# Sheet1.net
KiCad netlist of a schematic drawn in Altium Designer
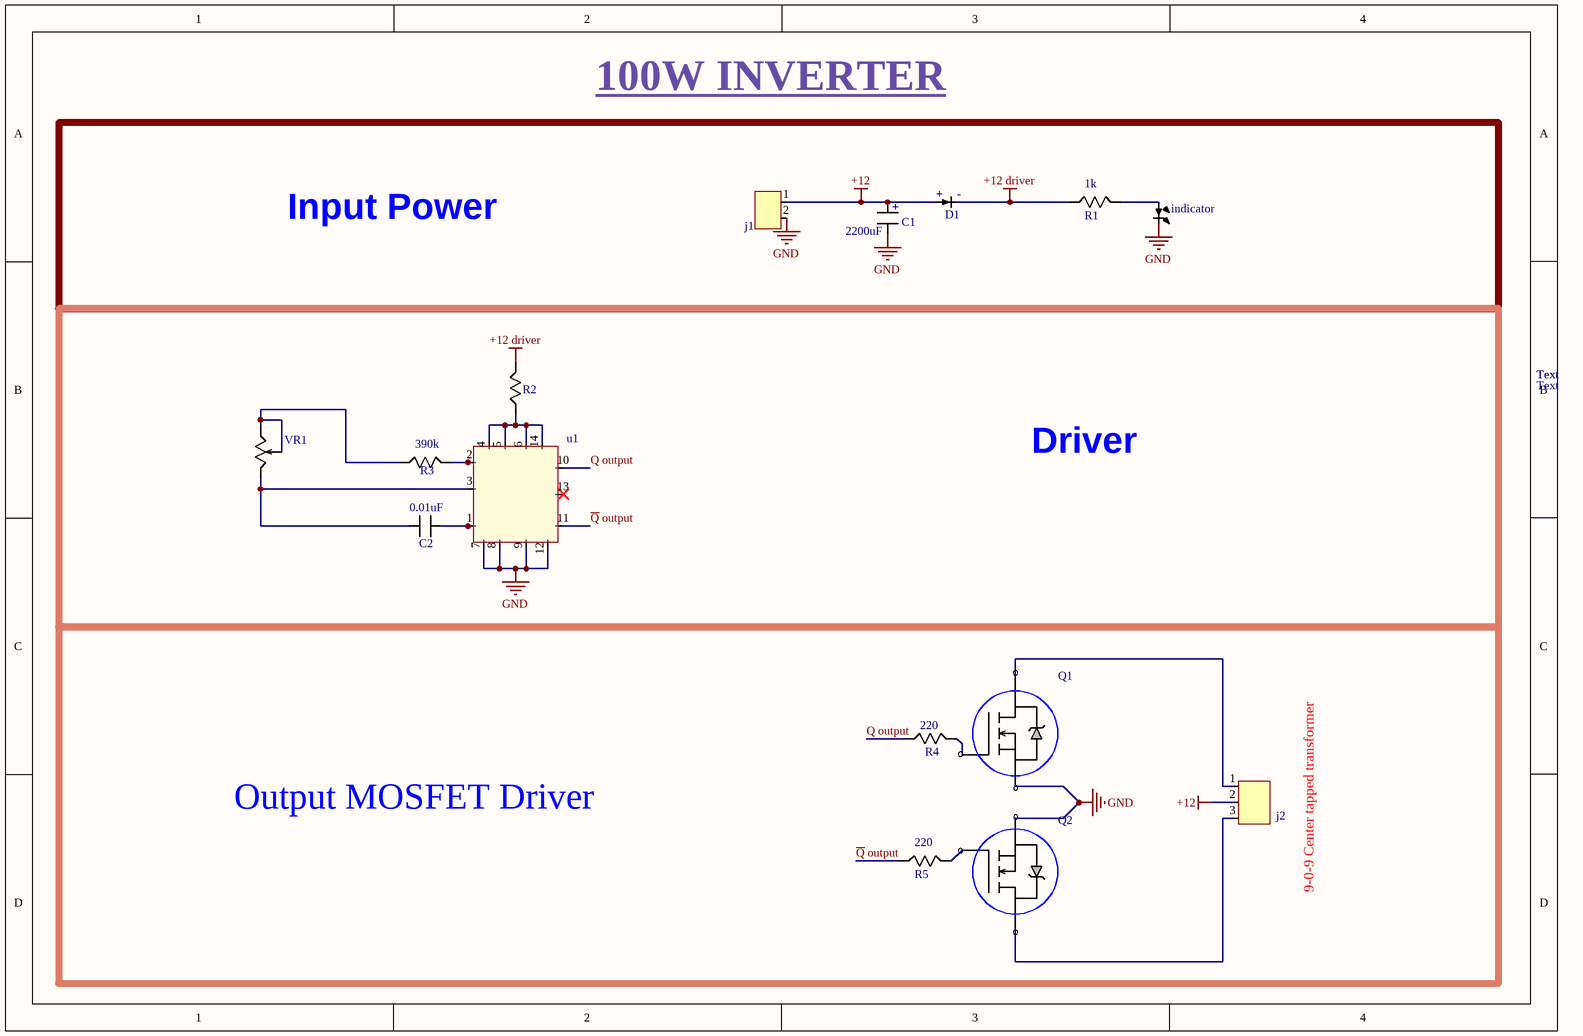
[diagram p0: Sheet1.SchDoc]

(export (version "E")
  (design (tool "Eeschema 10.0.6"))
  (components
    (comp (ref "1")
      (value "D1")
      (footprint "1N4007_TH_D")
      (description "Diode Switching 1KV 1A 2-Pin DO-41 T/R")
      (libsource (lib "Sch_common.~(3)") (part "D_1N400_th"))
    )
    (comp (ref "C1")
      (value "2200uF")
      (footprint "2200uF_35V_Ely_TH")
      (fields (field (name "TOLERANCE") "20%"))
      (libsource (lib "Sch_common.~(3)") (part "C_2200uF_Ely_35V_TH"))
    )
    (comp (ref "C2")
      (value "0.01uF")
      (footprint "0.01uF_cer_th_C - duplicate1")
      (description "Capacitor Ceramic 0.01uF 50V C0G 5% 5mm T/R")
      (fields (field (name "TOLERANCE") "5%"))
      (libsource (lib "Sch_common.~(3)") (part "C_0.01uF_Cer_50V_TH"))
    )
    (comp (ref "indicator")
      (value "LED_3mm_red_TH")
      (footprint "LED_red_TH")
      (libsource (lib "Sch_common.~(3)") (part "LED_3mm_red_TH"))
    )
    (comp (ref "j1")
      (value "2P_5mm_TH")
      (footprint "2pin_5mm_TH")
      (description "TERM BLOCK PLUG 2POS 90DEG 5MM")
      (fields (field (name "VOLTAGE") "300V"))
      (libsource (lib "Sch_common.~(3)") (part "2P_5mm_TH"))
    )
    (comp (ref "j2")
      (value "3pin_5mm_TH")
      (footprint "3pin_5mm_TH")
      (description "Connector Terminal Blocks Female 3 Position 5mm Screw Straig")
      (fields (field (name "VOLTAGE") "300V"))
      (libsource (lib "Sch_common.~(3)") (part "3pin_5mm_TH"))
    )
    (comp (ref "Q1")
      (value "IRF540ZLPBF")
      (footprint "IRF540_TH_MOS")
      (description "Mosfet, Power; N-ch; Vdss 100V; Rds(on) 21MILLIOHMS; Id 36A; TO-262; Pd 92W; Vgs +/-20")
      (libsource (lib "Sch_common.~(3)") (part "IRF540ZLPBF"))
    )
    (comp (ref "Q2")
      (value "IRF540ZLPBF")
      (footprint "IRF540_TH_MOS")
      (description "Mosfet, Power; N-ch; Vdss 100V; Rds(on) 21MILLIOHMS; Id 36A; TO-262; Pd 92W; Vgs +/-20")
      (libsource (lib "Sch_common.~(3)") (part "IRF540ZLPBF"))
    )
    (comp (ref "R1")
      (value "1k")
      (footprint "1k_0.25_th_R")
      (description "TE Connectivity CFR16 Series Axial Carbon Film Resistor 1k 5% 0.25W -1200  0ppm/C")
      (fields (field (name "TOLERANCE") "5%"))
      (libsource (lib "Sch_common.~(3)") (part "R_1K_0.25W_TH"))
    )
    (comp (ref "R2")
      (value "R_330_0.25W_TH")
      (footprint "330ohm_th_R")
      (description "TE Connectivity CFR16 Series Axial Carbon Film Resistor 330 5% 0.25W -1200  0ppm/C")
      (fields (field (name "TOLERANCE") "5%"))
      (libsource (lib "Sch_common.~(3)") (part "R_330_0.25W_TH"))
    )
    (comp (ref "R3")
      (value "390k")
      (footprint "390ohm_0.25w_th_R")
      (description "RES 390K OHM 1/4W 5% AXIAL")
      (fields (field (name "TOLERANCE") "5%"))
      (libsource (lib "Sch_common.~(3)") (part "R_390K_0.25W_TH"))
    )
    (comp (ref "R4")
      (value "220")
      (footprint "220ohm_0.25_th_R")
      (description "RES 220 OHM 1/4W 5% AXIAL")
      (fields (field (name "TOLERANCE") "5%"))
      (libsource (lib "Sch_common.~(3)") (part "R_220_0.25W_TH"))
    )
    (comp (ref "R5")
      (value "220")
      (footprint "220ohm_0.25_th_R")
      (description "RES 220 OHM 1/4W 5% AXIAL")
      (fields (field (name "TOLERANCE") "5%"))
      (libsource (lib "Sch_common.~(3)") (part "R_220_0.25W_TH"))
    )
    (comp (ref "u1")
      (value "CD4047BE IC")
      (footprint "CD4047_TH_IC")
      (libsource (lib "Sch_common.~(3)") (part "CD4047BE IC"))
    )
    (comp (ref "VR1")
      (value "VR_1K_trim_20T")
      (footprint "1k_var_th_R")
      (description "TRIMMER 1K OHM 1W PC PIN")
      (fields (field (name "TOLERANCE") "5%"))
      (libsource (lib "Sch_common.~(3)") (part "VR_1K_trim_20T"))
    )
  )
  (nets
    (net (code "1") (name "+12") (class "Default")
      (node (ref "1") (pin "1") (pintype "passive"))
      (node (ref "C1") (pin "1") (pinfunction "1_1") (pintype "passive"))
      (node (ref "j1") (pin "1") (pinfunction "1_1") (pintype "passive"))
      (node (ref "j2") (pin "2") (pinfunction "2_2") (pintype "passive"))
    )
    (net (code "2") (name "+12 driver") (class "Default")
      (node (ref "1") (pin "2") (pintype "passive"))
      (node (ref "R1") (pin "1") (pinfunction "1_1") (pintype "passive"))
      (node (ref "R2") (pin "2") (pinfunction "2_2") (pintype "passive"))
    )
    (net (code "3") (name "/Q output") (class "Default")
      (node (ref "R4") (pin "1") (pinfunction "1_1") (pintype "passive"))
      (node (ref "u1") (pin "10") (pinfunction "Q_10") (pintype "passive"))
    )
    (net (code "4") (name "/~{Q} output") (class "Default")
      (node (ref "R5") (pin "1") (pinfunction "1_1") (pintype "passive"))
      (node (ref "u1") (pin "11") (pinfunction "~{Q}_11") (pintype "passive"))
    )
    (net (code "5") (name "GND") (class "Default")
      (node (ref "C1") (pin "2") (pinfunction "2_2") (pintype "passive"))
      (node (ref "Q1") (pin "3") (pinfunction "3_3") (pintype "passive"))
      (node (ref "Q2") (pin "3") (pinfunction "3_3") (pintype "passive"))
      (node (ref "indicator") (pin "2") (pintype "passive"))
      (node (ref "j1") (pin "2") (pinfunction "2_2") (pintype "passive"))
      (node (ref "u1") (pin "12") (pinfunction "RETREGGER_12") (pintype "passive"))
      (node (ref "u1") (pin "7") (pinfunction "VSS_7") (pintype "passive"))
      (node (ref "u1") (pin "8") (pinfunction "+TREGGER_8") (pintype "passive"))
      (node (ref "u1") (pin "9") (pinfunction "EXT_RETREGGER_9") (pintype "passive"))
    )
    (net (code "6") (name "Net-(Q1-Pad1)") (class "Default")
      (node (ref "Q1") (pin "1") (pinfunction "1_1") (pintype "passive"))
      (node (ref "R4") (pin "2") (pinfunction "2_2") (pintype "passive"))
    )
    (net (code "7") (name "Net-(Q1-Pad2)") (class "Default")
      (node (ref "Q1") (pin "2") (pinfunction "2_2") (pintype "passive"))
      (node (ref "j2") (pin "1") (pinfunction "1_1") (pintype "passive"))
    )
    (net (code "8") (name "Net-(Q2-Pad1)") (class "Default")
      (node (ref "Q2") (pin "1") (pinfunction "1_1") (pintype "passive"))
      (node (ref "R5") (pin "2") (pinfunction "2_2") (pintype "passive"))
    )
    (net (code "9") (name "Net-(Q2-Pad2)") (class "Default")
      (node (ref "Q2") (pin "2") (pinfunction "2_2") (pintype "passive"))
      (node (ref "j2") (pin "3") (pinfunction "3_3") (pintype "passive"))
    )
    (net (code "10") (name "Net-(R1-Pad2)") (class "Default")
      (node (ref "R1") (pin "2") (pinfunction "2_2") (pintype "passive"))
      (node (ref "indicator") (pin "1") (pintype "passive"))
    )
    (net (code "11") (name "Net-(R3-Pad1)") (class "Default")
      (node (ref "R3") (pin "1") (pinfunction "1_1") (pintype "passive"))
      (node (ref "VR1") (pin "1") (pinfunction "1_1") (pintype "passive"))
      (node (ref "VR1") (pin "3") (pinfunction "3_3") (pintype "passive"))
    )
    (net (code "12") (name "Net-(u1--TRIGGER)") (class "Default")
      (node (ref "R2") (pin "1") (pinfunction "1_1") (pintype "passive"))
      (node (ref "u1") (pin "14") (pinfunction "VDD_14") (pintype "passive"))
      (node (ref "u1") (pin "4") (pinfunction "~{ASTABL}E_4") (pintype "passive"))
      (node (ref "u1") (pin "5") (pinfunction "ASTABLE_5") (pintype "passive"))
      (node (ref "u1") (pin "6") (pinfunction "-TRIGGER_6") (pintype "passive"))
    )
    (net (code "13") (name "Net-(u1-C)") (class "Default")
      (node (ref "C2") (pin "2") (pinfunction "2_2") (pintype "passive"))
      (node (ref "u1") (pin "1") (pinfunction "C_1") (pintype "passive"))
    )
    (net (code "14") (name "Net-(u1-R)") (class "Default")
      (node (ref "R3") (pin "2") (pinfunction "2_2") (pintype "passive"))
      (node (ref "u1") (pin "2") (pinfunction "R_2") (pintype "passive"))
    )
    (net (code "15") (name "Net-(u1-R-C_common)") (class "Default")
      (node (ref "C2") (pin "1") (pinfunction "1_1") (pintype "passive"))
      (node (ref "VR1") (pin "2") (pinfunction "2_2") (pintype "passive"))
      (node (ref "u1") (pin "3") (pinfunction "R-C_common_3") (pintype "passive"))
    )
    (net (code "16") (name "unconnected-(u1-OSC_OUT-Pad13)") (class "Default")
      (node (ref "u1") (pin "13") (pinfunction "OSC_OUT_13") (pintype "passive+no_connect"))
    )
  )
)
